# schematics.net
KiCad netlist of a schematic drawn in EasyEDA
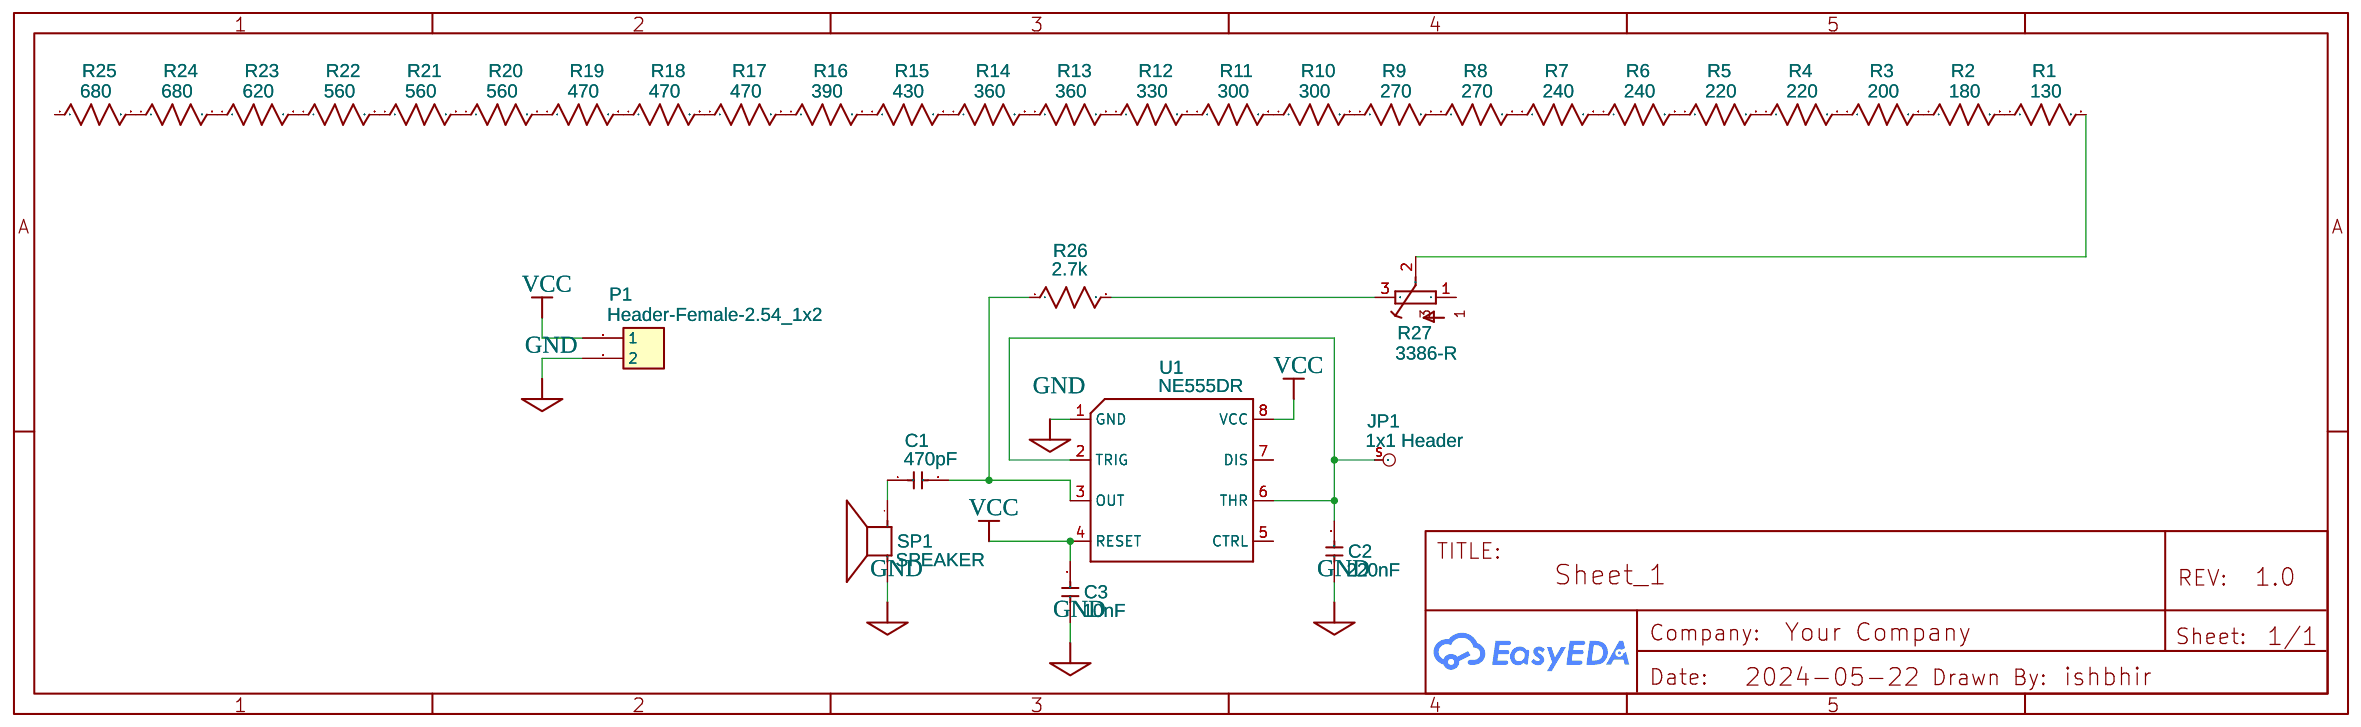
[diagram p0: schematic sheet]

(export (version "E")
  (design (tool "Eeschema 10.0.6"))
  (components
    (comp (ref "C1")
      (value "470pF")
      (fields (field (name "Manufacturer Part") "GRM1885C2A471JA01D"))
      (libsource (lib "") (part "Unknown_470_690"))
    )
    (comp (ref "C2")
      (value "220nF")
      (fields (field (name "Manufacturer Part") "CC0603KRX7R8BB224"))
      (libsource (lib "") (part "Unknown_670_720"))
    )
    (comp (ref "C3")
      (value "10nF")
      (fields (field (name "Manufacturer Part") "CC0603KRX7R9BB103"))
      (libsource (lib "") (part "Unknown_540_740"))
    )
    (comp (ref "JP1")
      (value "1x1 Header")
      (fields (field (name "Manufacturer Part") "?"))
      (libsource (lib "") (part "Unknown_690_680"))
    )
    (comp (ref "P1")
      (value "Header-Female-2.54_1x2")
      (fields (field (name "Manufacturer") "LCSC"))
      (libsource (lib "") (part "Unknown_310_630"))
    )
    (comp (ref "R1")
      (value "130")
      (fields (field (name "Manufacturer Part") "?"))
      (libsource (lib "") (part "Resistor"))
    )
    (comp (ref "R2")
      (value "180")
      (fields (field (name "Manufacturer Part") "?"))
      (libsource (lib "") (part "Resistor"))
    )
    (comp (ref "R3")
      (value "200")
      (fields (field (name "Manufacturer Part") "?"))
      (libsource (lib "") (part "Resistor"))
    )
    (comp (ref "R4")
      (value "220")
      (fields (field (name "Manufacturer Part") "?"))
      (libsource (lib "") (part "Resistor"))
    )
    (comp (ref "R5")
      (value "220")
      (fields (field (name "Manufacturer Part") "?"))
      (libsource (lib "") (part "Resistor"))
    )
    (comp (ref "R6")
      (value "240")
      (fields (field (name "Manufacturer Part") "?"))
      (libsource (lib "") (part "Resistor"))
    )
    (comp (ref "R7")
      (value "240")
      (fields (field (name "Manufacturer Part") "?"))
      (libsource (lib "") (part "Resistor"))
    )
    (comp (ref "R8")
      (value "270")
      (fields (field (name "Manufacturer Part") "?"))
      (libsource (lib "") (part "Resistor"))
    )
    (comp (ref "R9")
      (value "270")
      (fields (field (name "Manufacturer Part") "?"))
      (libsource (lib "") (part "Resistor"))
    )
    (comp (ref "R10")
      (value "300")
      (fields (field (name "Manufacturer Part") "?"))
      (libsource (lib "") (part "Resistor"))
    )
    (comp (ref "R11")
      (value "300")
      (fields (field (name "Manufacturer Part") "?"))
      (libsource (lib "") (part "Resistor"))
    )
    (comp (ref "R12")
      (value "330")
      (fields (field (name "Manufacturer Part") "?"))
      (libsource (lib "") (part "Resistor"))
    )
    (comp (ref "R13")
      (value "360")
      (fields (field (name "Manufacturer Part") "?"))
      (libsource (lib "") (part "Resistor"))
    )
    (comp (ref "R14")
      (value "360")
      (fields (field (name "Manufacturer Part") "?"))
      (libsource (lib "") (part "Resistor"))
    )
    (comp (ref "R15")
      (value "430")
      (fields (field (name "Manufacturer Part") "?"))
      (libsource (lib "") (part "Resistor"))
    )
    (comp (ref "R16")
      (value "390")
      (fields (field (name "Manufacturer Part") "?"))
      (libsource (lib "") (part "Resistor"))
    )
    (comp (ref "R17")
      (value "470")
      (fields (field (name "Manufacturer Part") "?"))
      (libsource (lib "") (part "Resistor"))
    )
    (comp (ref "R18")
      (value "470")
      (fields (field (name "Manufacturer Part") "?"))
      (libsource (lib "") (part "Resistor"))
    )
    (comp (ref "R19")
      (value "470")
      (fields (field (name "Manufacturer Part") "?"))
      (libsource (lib "") (part "Resistor"))
    )
    (comp (ref "R20")
      (value "560")
      (fields (field (name "Manufacturer Part") "?"))
      (libsource (lib "") (part "Resistor"))
    )
    (comp (ref "R21")
      (value "560")
      (fields (field (name "Manufacturer Part") "?"))
      (libsource (lib "") (part "Resistor"))
    )
    (comp (ref "R22")
      (value "560")
      (fields (field (name "Manufacturer Part") "?"))
      (libsource (lib "") (part "Resistor"))
    )
    (comp (ref "R23")
      (value "620")
      (fields (field (name "Manufacturer Part") "?"))
      (libsource (lib "") (part "Resistor"))
    )
    (comp (ref "R24")
      (value "680")
      (fields (field (name "Manufacturer Part") "?"))
      (libsource (lib "") (part "Resistor"))
    )
    (comp (ref "R25")
      (value "680")
      (fields (field (name "Manufacturer Part") "?"))
      (libsource (lib "") (part "Resistor"))
    )
    (comp (ref "R26")
      (value "2.7k")
      (fields (field (name "Manufacturer Part") "?"))
      (libsource (lib "") (part "Resistor"))
    )
    (comp (ref "R27")
      (value "3386-R")
      (fields (field (name "Manufacturer Part") "?"))
      (libsource (lib "") (part "Unknown_710_600"))
    )
    (comp (ref "SP1")
      (value "SPEAKER")
      (fields (field (name "Manufacturer Part") "?"))
      (libsource (lib "") (part "Unknown_450_720"))
    )
    (comp (ref "U1") (value "NE555DR") (libsource (lib "") (part "Unknown_590_690")))
  )
  (nets
    (net (code "1") (name "GND") (class "Default")
      (node (ref "C2") (pin "1") (pinfunction "1_1") (pintype "unspecified"))
      (node (ref "C3") (pin "1") (pinfunction "1_1") (pintype "unspecified"))
      (node (ref "P1") (pin "2") (pinfunction "2_2") (pintype "input"))
      (node (ref "SP1") (pin "+") (pinfunction "+_+") (pintype "unspecified"))
      (node (ref "U1") (pin "1") (pinfunction "GND_1") (pintype "unspecified"))
    )
    (net (code "2") (name "Net-(C1-Pad1)") (class "Default")
      (node (ref "C1") (pin "1") (pinfunction "1_1") (pintype "unspecified"))
      (node (ref "SP1") (pin "-") (pinfunction "-_-") (pintype "unspecified"))
    )
    (net (code "3") (name "Net-(R1-Pad1)") (class "Default")
      (node (ref "R1") (pin "1") (pinfunction "1_1") (pintype "unspecified"))
      (node (ref "R2") (pin "2") (pinfunction "2_2") (pintype "unspecified"))
    )
    (net (code "4") (name "Net-(R1-Pad2)") (class "Default")
      (node (ref "R1") (pin "2") (pinfunction "2_2") (pintype "unspecified"))
      (node (ref "R27") (pin "2") (pinfunction "2_2") (pintype "unspecified"))
    )
    (net (code "5") (name "Net-(R2-Pad1)") (class "Default")
      (node (ref "R2") (pin "1") (pinfunction "1_1") (pintype "unspecified"))
      (node (ref "R3") (pin "2") (pinfunction "2_2") (pintype "unspecified"))
    )
    (net (code "6") (name "Net-(R3-Pad1)") (class "Default")
      (node (ref "R3") (pin "1") (pinfunction "1_1") (pintype "unspecified"))
      (node (ref "R4") (pin "2") (pinfunction "2_2") (pintype "unspecified"))
    )
    (net (code "7") (name "Net-(R4-Pad1)") (class "Default")
      (node (ref "R4") (pin "1") (pinfunction "1_1") (pintype "unspecified"))
      (node (ref "R5") (pin "2") (pinfunction "2_2") (pintype "unspecified"))
    )
    (net (code "8") (name "Net-(R5-Pad1)") (class "Default")
      (node (ref "R5") (pin "1") (pinfunction "1_1") (pintype "unspecified"))
      (node (ref "R6") (pin "2") (pinfunction "2_2") (pintype "unspecified"))
    )
    (net (code "9") (name "Net-(R6-Pad1)") (class "Default")
      (node (ref "R6") (pin "1") (pinfunction "1_1") (pintype "unspecified"))
      (node (ref "R7") (pin "2") (pinfunction "2_2") (pintype "unspecified"))
    )
    (net (code "10") (name "Net-(R7-Pad1)") (class "Default")
      (node (ref "R7") (pin "1") (pinfunction "1_1") (pintype "unspecified"))
      (node (ref "R8") (pin "2") (pinfunction "2_2") (pintype "unspecified"))
    )
    (net (code "11") (name "Net-(R8-Pad1)") (class "Default")
      (node (ref "R8") (pin "1") (pinfunction "1_1") (pintype "unspecified"))
      (node (ref "R9") (pin "2") (pinfunction "2_2") (pintype "unspecified"))
    )
    (net (code "12") (name "Net-(R10-Pad1)") (class "Default")
      (node (ref "R10") (pin "1") (pinfunction "1_1") (pintype "unspecified"))
      (node (ref "R11") (pin "2") (pinfunction "2_2") (pintype "unspecified"))
    )
    (net (code "13") (name "Net-(R10-Pad2)") (class "Default")
      (node (ref "R10") (pin "2") (pinfunction "2_2") (pintype "unspecified"))
      (node (ref "R9") (pin "1") (pinfunction "1_1") (pintype "unspecified"))
    )
    (net (code "14") (name "Net-(R11-Pad1)") (class "Default")
      (node (ref "R11") (pin "1") (pinfunction "1_1") (pintype "unspecified"))
      (node (ref "R12") (pin "2") (pinfunction "2_2") (pintype "unspecified"))
    )
    (net (code "15") (name "Net-(R12-Pad1)") (class "Default")
      (node (ref "R12") (pin "1") (pinfunction "1_1") (pintype "unspecified"))
      (node (ref "R13") (pin "2") (pinfunction "2_2") (pintype "unspecified"))
    )
    (net (code "16") (name "Net-(R13-Pad1)") (class "Default")
      (node (ref "R13") (pin "1") (pinfunction "1_1") (pintype "unspecified"))
      (node (ref "R14") (pin "2") (pinfunction "2_2") (pintype "unspecified"))
    )
    (net (code "17") (name "Net-(R14-Pad1)") (class "Default")
      (node (ref "R14") (pin "1") (pinfunction "1_1") (pintype "unspecified"))
      (node (ref "R15") (pin "2") (pinfunction "2_2") (pintype "unspecified"))
    )
    (net (code "18") (name "Net-(R15-Pad1)") (class "Default")
      (node (ref "R15") (pin "1") (pinfunction "1_1") (pintype "unspecified"))
      (node (ref "R16") (pin "2") (pinfunction "2_2") (pintype "unspecified"))
    )
    (net (code "19") (name "Net-(R16-Pad1)") (class "Default")
      (node (ref "R16") (pin "1") (pinfunction "1_1") (pintype "unspecified"))
      (node (ref "R17") (pin "2") (pinfunction "2_2") (pintype "unspecified"))
    )
    (net (code "20") (name "Net-(R17-Pad1)") (class "Default")
      (node (ref "R17") (pin "1") (pinfunction "1_1") (pintype "unspecified"))
      (node (ref "R18") (pin "2") (pinfunction "2_2") (pintype "unspecified"))
    )
    (net (code "21") (name "Net-(R18-Pad1)") (class "Default")
      (node (ref "R18") (pin "1") (pinfunction "1_1") (pintype "unspecified"))
      (node (ref "R19") (pin "2") (pinfunction "2_2") (pintype "unspecified"))
    )
    (net (code "22") (name "Net-(R19-Pad1)") (class "Default")
      (node (ref "R19") (pin "1") (pinfunction "1_1") (pintype "unspecified"))
      (node (ref "R20") (pin "2") (pinfunction "2_2") (pintype "unspecified"))
    )
    (net (code "23") (name "Net-(R20-Pad1)") (class "Default")
      (node (ref "R20") (pin "1") (pinfunction "1_1") (pintype "unspecified"))
      (node (ref "R21") (pin "2") (pinfunction "2_2") (pintype "unspecified"))
    )
    (net (code "24") (name "Net-(R21-Pad1)") (class "Default")
      (node (ref "R21") (pin "1") (pinfunction "1_1") (pintype "unspecified"))
      (node (ref "R22") (pin "2") (pinfunction "2_2") (pintype "unspecified"))
    )
    (net (code "25") (name "Net-(R22-Pad1)") (class "Default")
      (node (ref "R22") (pin "1") (pinfunction "1_1") (pintype "unspecified"))
      (node (ref "R23") (pin "2") (pinfunction "2_2") (pintype "unspecified"))
    )
    (net (code "26") (name "Net-(R23-Pad1)") (class "Default")
      (node (ref "R23") (pin "1") (pinfunction "1_1") (pintype "unspecified"))
      (node (ref "R24") (pin "2") (pinfunction "2_2") (pintype "unspecified"))
    )
    (net (code "27") (name "Net-(R24-Pad1)") (class "Default")
      (node (ref "R24") (pin "1") (pinfunction "1_1") (pintype "unspecified"))
      (node (ref "R25") (pin "2") (pinfunction "2_2") (pintype "unspecified"))
    )
    (net (code "28") (name "Net-(R26-Pad2)") (class "Default")
      (node (ref "R26") (pin "2") (pinfunction "2_2") (pintype "unspecified"))
      (node (ref "R27") (pin "3") (pinfunction "3_3") (pintype "unspecified"))
    )
    (net (code "29") (name "Net-(U1-OUT)") (class "Default")
      (node (ref "C1") (pin "2") (pinfunction "2_2") (pintype "unspecified"))
      (node (ref "R26") (pin "1") (pinfunction "1_1") (pintype "unspecified"))
      (node (ref "U1") (pin "3") (pinfunction "OUT_3") (pintype "unspecified"))
    )
    (net (code "30") (name "Net-(U1-THR)") (class "Default")
      (node (ref "C2") (pin "2") (pinfunction "2_2") (pintype "unspecified"))
      (node (ref "JP1") (pin "S") (pinfunction "S_S") (pintype "unspecified"))
      (node (ref "U1") (pin "2") (pinfunction "TRIG_2") (pintype "unspecified"))
      (node (ref "U1") (pin "6") (pinfunction "THR_6") (pintype "unspecified"))
    )
    (net (code "31") (name "VCC") (class "Default")
      (node (ref "C3") (pin "2") (pinfunction "2_2") (pintype "unspecified"))
      (node (ref "P1") (pin "1") (pinfunction "1_1") (pintype "input"))
      (node (ref "U1") (pin "4") (pinfunction "RESET_4") (pintype "unspecified"))
      (node (ref "U1") (pin "8") (pinfunction "VCC_8") (pintype "unspecified"))
    )
    (net (code "32") (name "unconnected-(R25-Pad1)") (class "Default")
      (node (ref "R25") (pin "1") (pinfunction "1_1") (pintype "unspecified"))
    )
    (net (code "33") (name "unconnected-(R27-Pad1)") (class "Default")
      (node (ref "R27") (pin "1") (pinfunction "1_1") (pintype "unspecified"))
    )
    (net (code "34") (name "unconnected-(U1-CTRL-Pad5)") (class "Default")
      (node (ref "U1") (pin "5") (pinfunction "CTRL_5") (pintype "unspecified"))
    )
    (net (code "35") (name "unconnected-(U1-DIS-Pad7)") (class "Default")
      (node (ref "U1") (pin "7") (pinfunction "DIS_7") (pintype "unspecified"))
    )
  )
)
